# isolator.net
KiCad netlist of a schematic drawn in Altium Designer
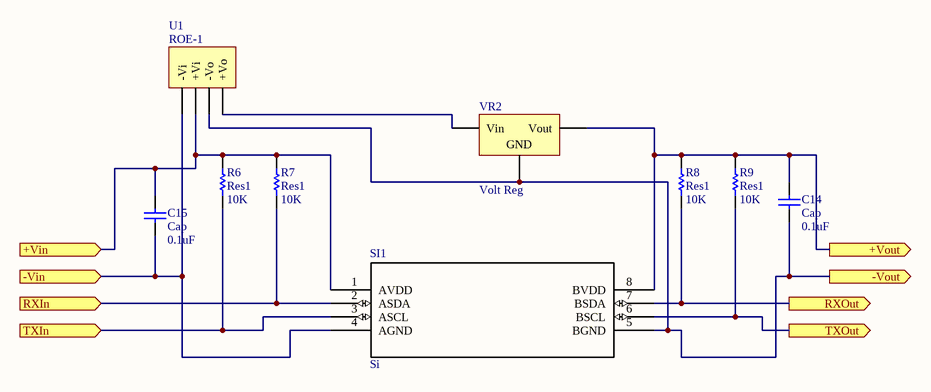
[diagram p0: isolator.SchDoc]

(export (version "E")
  (design (tool "Eeschema 10.0.6"))
  (components
    (comp (ref "C14")
      (value "Cap")
      (footprint "C0805")
      (description "Capacitor")
      (fields (field (name "ALTIUM_VALUE") "0.1uF") (field (name "PUBLISHER") "Altium Limited"))
      (libsource (lib "Miscellaneous Devices") (part "Cap"))
    )
    (comp (ref "C15")
      (value "Cap")
      (footprint "C0805")
      (description "Capacitor")
      (fields (field (name "ALTIUM_VALUE") "0.1uF") (field (name "PUBLISHER") "Altium Limited"))
      (libsource (lib "Miscellaneous Devices") (part "Cap"))
    )
    (comp (ref "R6")
      (value "Res1")
      (footprint "0805R-10K")
      (description "Resistor")
      (fields (field (name "ALTIUM_VALUE") "10K") (field (name "PUBLISHER") "Altium Limited"))
      (libsource (lib "Miscellaneous Devices") (part "Res1"))
    )
    (comp (ref "R7")
      (value "Res1")
      (footprint "0805R-10K")
      (description "Resistor")
      (fields (field (name "ALTIUM_VALUE") "10K") (field (name "PUBLISHER") "Altium Limited"))
      (libsource (lib "Miscellaneous Devices") (part "Res1"))
    )
    (comp (ref "R8")
      (value "Res1")
      (footprint "0805R-10K")
      (description "Resistor")
      (fields (field (name "ALTIUM_VALUE") "10K") (field (name "PUBLISHER") "Altium Limited"))
      (libsource (lib "Miscellaneous Devices") (part "Res1"))
    )
    (comp (ref "R9")
      (value "Res1")
      (footprint "0805R-10K")
      (description "Resistor")
      (fields (field (name "ALTIUM_VALUE") "10K") (field (name "PUBLISHER") "Altium Limited"))
      (libsource (lib "Miscellaneous Devices") (part "Res1"))
    )
    (comp (ref "ROE-1")
      (value "U1")
      (footprint "HDR1X4")
      (description "Header, 4-Pin")
      (fields (field (name "PUBLISHER") "Altium Limited"))
      (libsource (lib "Miscellaneous Connectors") (part "Header 4"))
    )
    (comp (ref "SI1")
      (value "Si")
      (footprint "SOIC-8")
      (description "Imported")
      (libsource (lib "2014-11-27_19-10-54") (part "Si8600AC-B-IS"))
    )
    (comp (ref "VR2")
      (value "Volt Reg")
      (footprint "SOT23-123")
      (description "Voltage Regulator")
      (fields (field (name "PUBLISHER") "Altium Limited"))
      (libsource (lib "Miscellaneous Devices") (part "Volt Reg"))
    )
  )
  (nets
    (net (code "1") (name "/+Vin") (class "Default")
      (node (ref "C15") (pin "2") (pinfunction "2_2") (pintype "passive"))
      (node (ref "R6") (pin "2") (pinfunction "2_2") (pintype "passive"))
      (node (ref "R7") (pin "2") (pinfunction "2_2") (pintype "passive"))
      (node (ref "ROE-1") (pin "2") (pinfunction "+Vi_2") (pintype "passive"))
      (node (ref "SI1") (pin "1") (pinfunction "AVDD_1") (pintype "passive"))
    )
    (net (code "2") (name "/+Vout") (class "Default")
      (node (ref "C14") (pin "2") (pinfunction "2_2") (pintype "passive"))
      (node (ref "R8") (pin "2") (pinfunction "2_2") (pintype "passive"))
      (node (ref "R9") (pin "2") (pinfunction "2_2") (pintype "passive"))
      (node (ref "SI1") (pin "8") (pinfunction "BVDD_8") (pintype "passive"))
      (node (ref "VR2") (pin "3") (pinfunction "Vout_3") (pintype "passive"))
    )
    (net (code "3") (name "/-Vin") (class "Default")
      (node (ref "C15") (pin "1") (pinfunction "1_1") (pintype "passive"))
      (node (ref "ROE-1") (pin "1") (pinfunction "-Vi_1") (pintype "passive"))
      (node (ref "SI1") (pin "4") (pinfunction "AGND_4") (pintype "passive"))
    )
    (net (code "4") (name "/-Vout") (class "Default")
      (node (ref "C14") (pin "1") (pinfunction "1_1") (pintype "passive"))
      (node (ref "ROE-1") (pin "3") (pinfunction "-Vo_3") (pintype "passive"))
      (node (ref "SI1") (pin "5") (pinfunction "BGND_5") (pintype "passive"))
      (node (ref "VR2") (pin "2") (pinfunction "GND_2") (pintype "passive"))
    )
    (net (code "5") (name "/RXIn") (class "Default")
      (node (ref "R7") (pin "1") (pinfunction "1_1") (pintype "passive"))
      (node (ref "SI1") (pin "2") (pinfunction "ASDA_2") (pintype "bidirectional"))
    )
    (net (code "6") (name "/RXOut") (class "Default")
      (node (ref "R8") (pin "1") (pinfunction "1_1") (pintype "passive"))
      (node (ref "SI1") (pin "7") (pinfunction "BSDA_7") (pintype "bidirectional"))
    )
    (net (code "7") (name "/TXIn") (class "Default")
      (node (ref "R6") (pin "1") (pinfunction "1_1") (pintype "passive"))
      (node (ref "SI1") (pin "3") (pinfunction "ASCL_3") (pintype "bidirectional"))
    )
    (net (code "8") (name "/TXOut") (class "Default")
      (node (ref "R9") (pin "1") (pinfunction "1_1") (pintype "passive"))
      (node (ref "SI1") (pin "6") (pinfunction "BSCL_6") (pintype "bidirectional"))
    )
    (net (code "9") (name "Net-(ROE-1-+Vo)") (class "Default")
      (node (ref "ROE-1") (pin "4") (pinfunction "+Vo_4") (pintype "passive"))
      (node (ref "VR2") (pin "1") (pinfunction "Vin_1") (pintype "passive"))
    )
  )
)
